# led-board.net
KiCad netlist of a schematic drawn in EAGLE
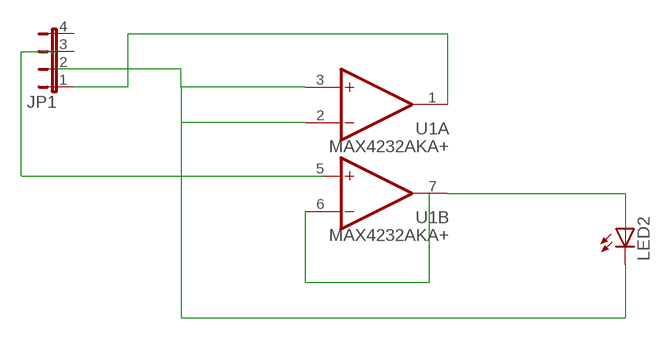
[diagram p0: schematic, sheet 1]

(export (version "E")
  (design (tool "Eeschema 10.0.6"))
  (components
    (comp (ref "JP1")
      (value "JP4E")
      (footprint "eagle-import:JP4")
      (libsource (lib "eagle-import") (part "JP4E"))
    )
    (comp (ref "LED2")
      (value "LEDCHIPLED-0603-TTW")
      (footprint "eagle-import:CHIPLED-0603-TTW")
      (libsource (lib "eagle-import") (part "LEDCHIPLED-0603-TTW"))
    )
    (comp (ref "U1")
      (value "MAX4232AKA+")
      (footprint "eagle-import:SOT23-8")
      (libsource (lib "eagle-import") (part "MAX4232AKA+"))
    )
  )
  (nets
    (net (code "1") (name "Net-(LED2-C)") (class "Default")
      (node (ref "LED2") (pin "C@1") (pinfunction "C_C@1") (pintype "passive"))
      (node (ref "U1") (pin "2") (pinfunction "-IN_2") (pintype "input"))
      (node (ref "U1") (pin "3") (pinfunction "+IN_3") (pintype "input"))
    )
    (net (code "2") (name "Net-(U1A-OUT)") (class "Default")
      (node (ref "JP1") (pin "1") (pinfunction "1_1") (pintype "passive"))
      (node (ref "U1") (pin "1") (pinfunction "OUT_1") (pintype "output"))
    )
    (net (code "3") (name "unconnected-(JP1-Pad2)") (class "Default")
      (node (ref "JP1") (pin "2") (pinfunction "2_2") (pintype "passive"))
    )
    (net (code "4") (name "unconnected-(JP1-Pad3)") (class "Default")
      (node (ref "JP1") (pin "3") (pinfunction "3_3") (pintype "passive"))
    )
    (net (code "5") (name "unconnected-(JP1-Pad4)") (class "Default")
      (node (ref "JP1") (pin "4") (pinfunction "4_4") (pintype "passive"))
    )
    (net (code "6") (name "unconnected-(LED2-A-PadA@1)") (class "Default")
      (node (ref "LED2") (pin "A@1") (pinfunction "A_A@1") (pintype "passive"))
    )
    (net (code "7") (name "unconnected-(U1B-+IN-Pad5)") (class "Default")
      (node (ref "U1") (pin "5") (pinfunction "+IN_5") (pintype "input"))
    )
    (net (code "8") (name "unconnected-(U1B--IN-Pad6)") (class "Default")
      (node (ref "U1") (pin "6") (pinfunction "-IN_6") (pintype "input"))
    )
    (net (code "9") (name "unconnected-(U1B-OUT-Pad7)") (class "Default")
      (node (ref "U1") (pin "7") (pinfunction "OUT_7") (pintype "output"))
    )
  )
)
